# SCH_swissarmyknife_2024-05-07.net
KiCad netlist of a schematic drawn in EasyEDA
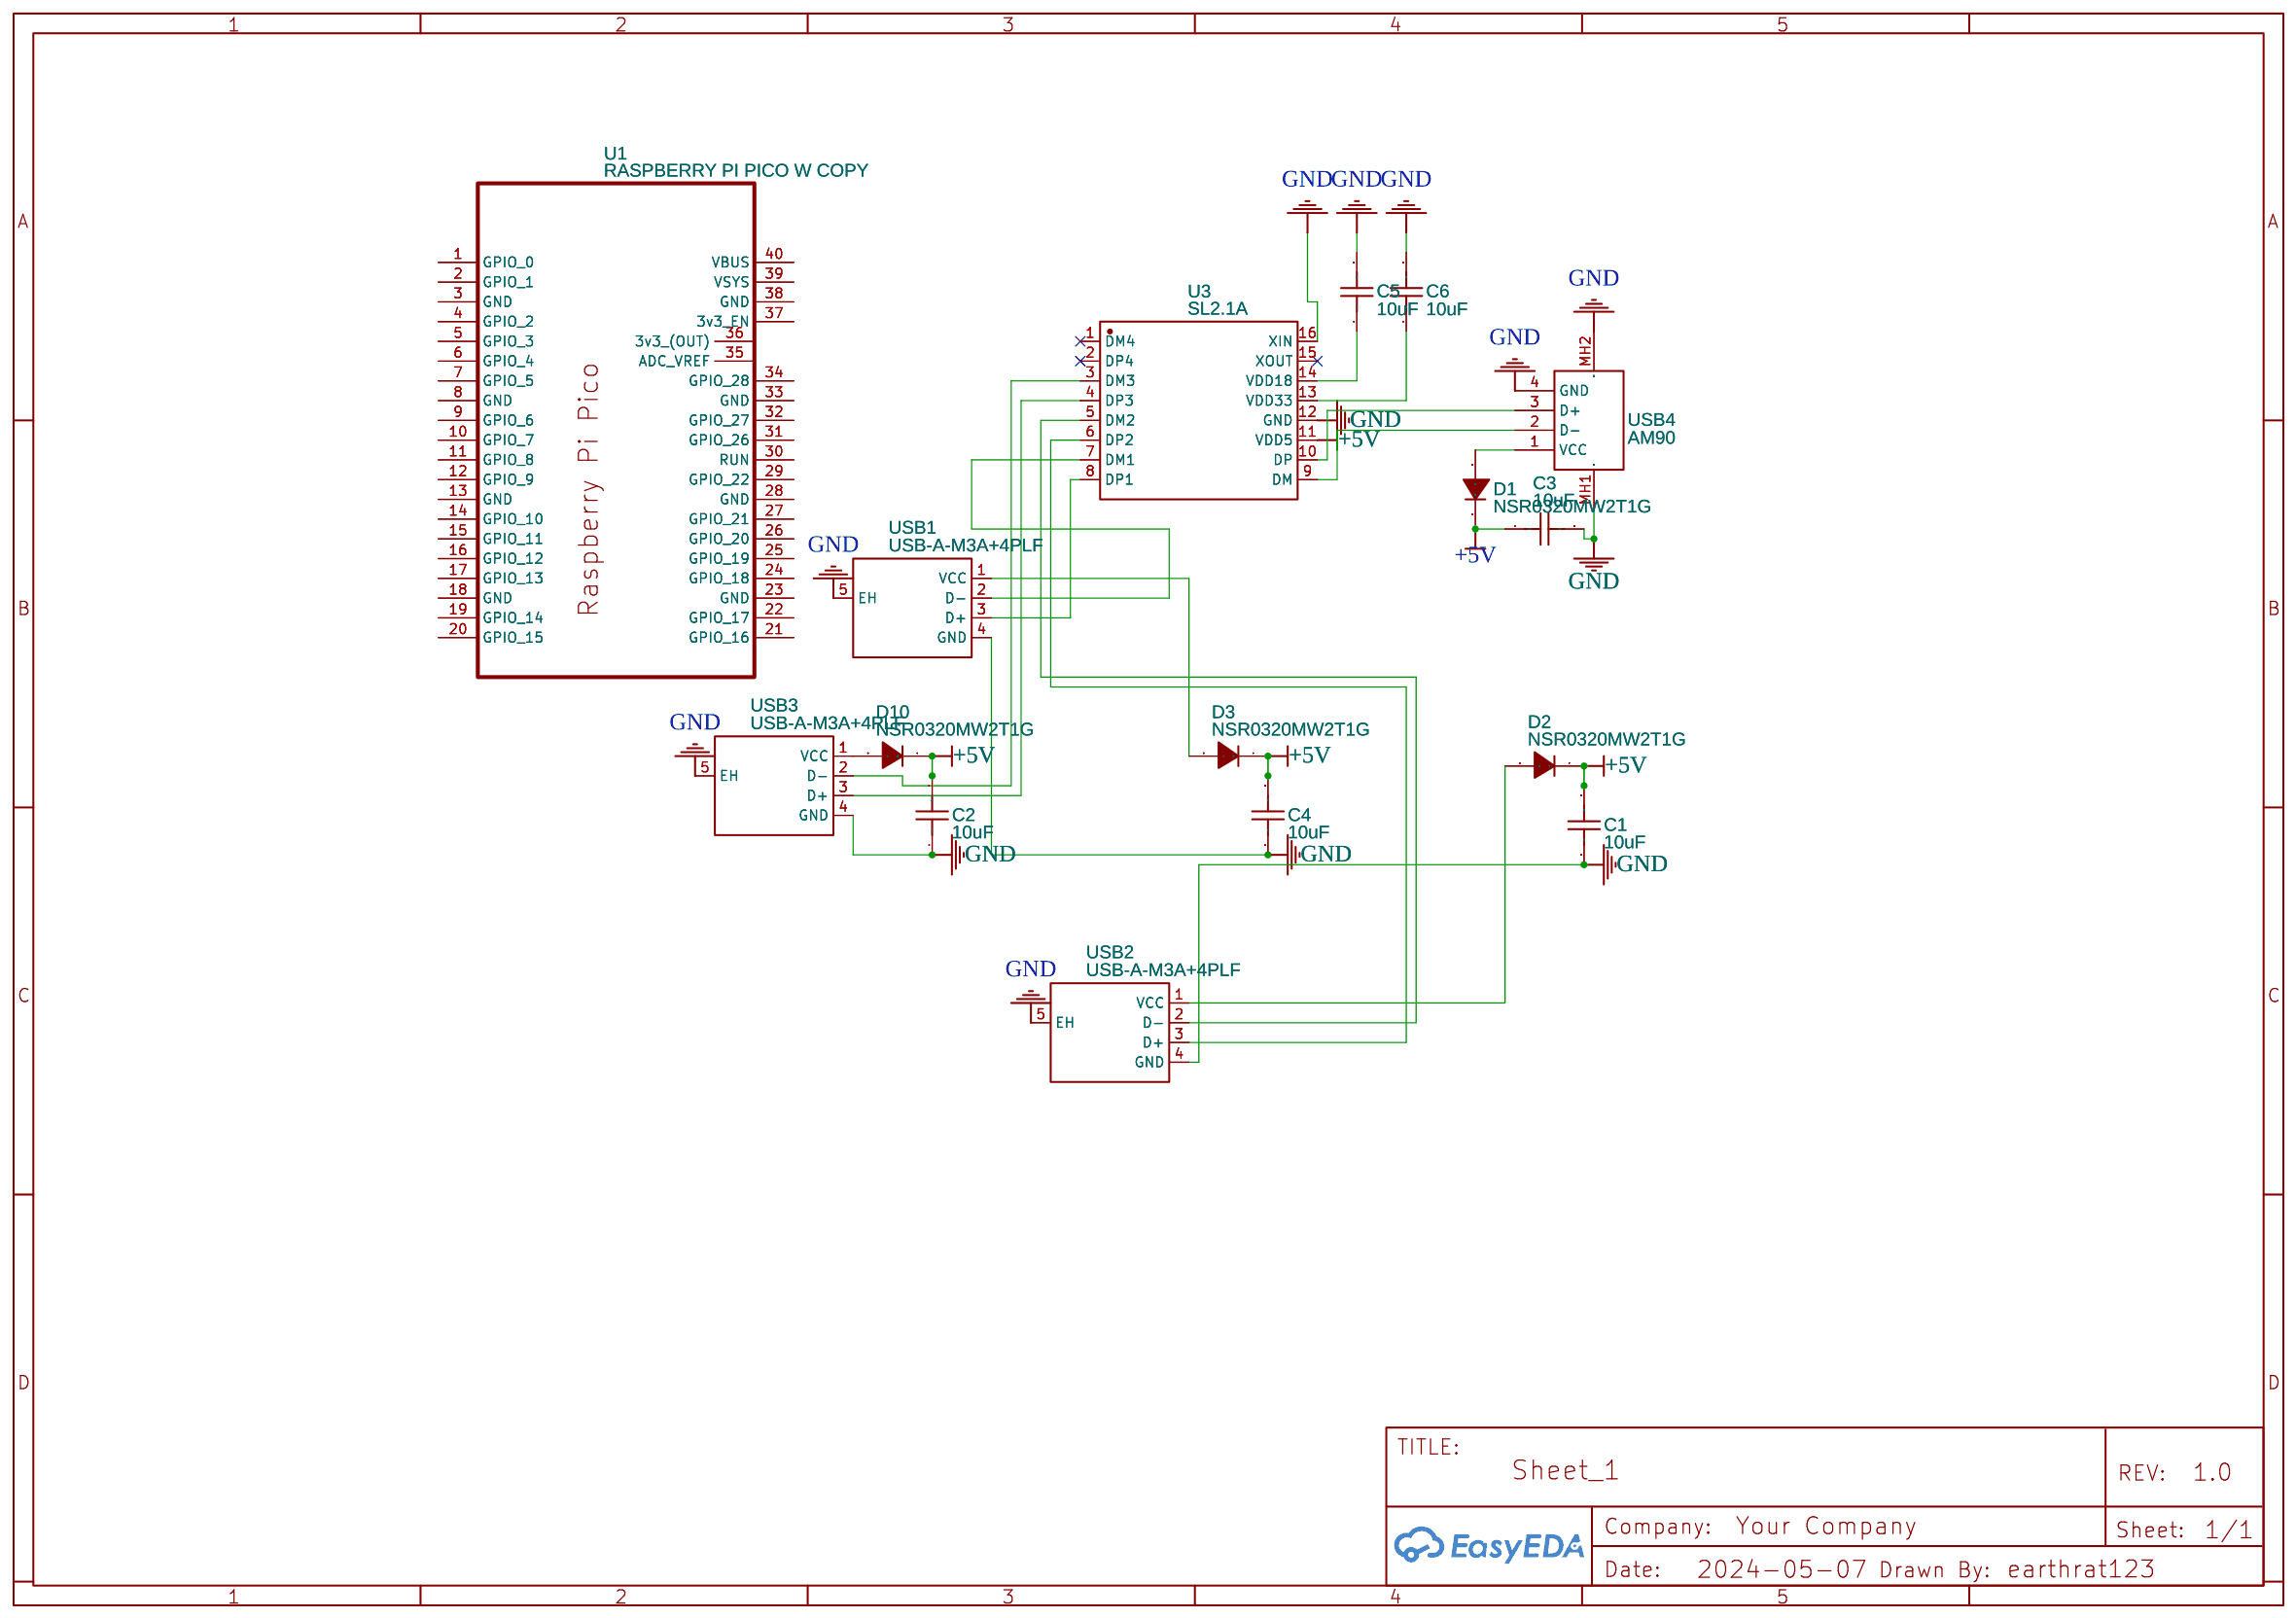
[diagram p0: schematic sheet]

(export (version "E")
  (design (tool "Eeschema 10.0.6"))
  (components
    (comp (ref "C1")
      (value "10uF")
      (fields
        (field (name "Manufacturer Part") "CL10A106KP8NNNC")
        (field (name "Manufacturer") "SAMSUNG(三星)")
      )
      (libsource (lib "") (part "CL10A106KP8NNNC"))
    )
    (comp (ref "C2")
      (value "10uF")
      (fields
        (field (name "Manufacturer Part") "CL10A106KP8NNNC")
        (field (name "Manufacturer") "SAMSUNG(三星)")
      )
      (libsource (lib "") (part "CL10A106KP8NNNC"))
    )
    (comp (ref "C3")
      (value "10uF")
      (fields
        (field (name "Manufacturer Part") "CL10A106KP8NNNC")
        (field (name "Manufacturer") "SAMSUNG(三星)")
      )
      (libsource (lib "") (part "CL10A106KP8NNNC_1"))
    )
    (comp (ref "C4")
      (value "10uF")
      (fields
        (field (name "Manufacturer Part") "CL10A106KP8NNNC")
        (field (name "Manufacturer") "SAMSUNG(三星)")
      )
      (libsource (lib "") (part "CL10A106KP8NNNC"))
    )
    (comp (ref "C5")
      (value "10uF")
      (fields
        (field (name "Manufacturer Part") "CL10A106KP8NNNC")
        (field (name "Manufacturer") "SAMSUNG(三星)")
      )
      (libsource (lib "") (part "CL10A106KP8NNNC"))
    )
    (comp (ref "C6")
      (value "10uF")
      (fields
        (field (name "Manufacturer Part") "CL10A106KP8NNNC")
        (field (name "Manufacturer") "SAMSUNG(三星)")
      )
      (libsource (lib "") (part "CL10A106KP8NNNC"))
    )
    (comp (ref "D1")
      (value "NSR0320MW2T1G")
      (fields (field (name "Manufacturer") "onsemi(安森美)"))
      (libsource (lib "") (part "NSR0320MW2T1G_1"))
    )
    (comp (ref "D2")
      (value "NSR0320MW2T1G")
      (fields (field (name "Manufacturer") "onsemi(安森美)"))
      (libsource (lib "") (part "NSR0320MW2T1G"))
    )
    (comp (ref "D3")
      (value "NSR0320MW2T1G")
      (fields (field (name "Manufacturer") "onsemi(安森美)"))
      (libsource (lib "") (part "NSR0320MW2T1G"))
    )
    (comp (ref "D10")
      (value "NSR0320MW2T1G")
      (fields (field (name "Manufacturer") "onsemi(安森美)"))
      (libsource (lib "") (part "NSR0320MW2T1G"))
    )
    (comp (ref "U1")
      (value "RASPBERRY PI PICO W COPY")
      (libsource (lib "") (part "RASPBERRY PI PICO W COPY"))
    )
    (comp (ref "U3")
      (value "SL2.1A")
      (fields (field (name "Manufacturer") "CoreChips(和芯润德)"))
      (libsource (lib "") (part "SL2.1A"))
    )
    (comp (ref "USB1")
      (value "USB-A-M3A+4PLF")
      (fields (field (name "Manufacturer") "JINJIA(金佳)"))
      (libsource (lib "") (part "USB-A-M3A+4PLF"))
    )
    (comp (ref "USB2")
      (value "USB-A-M3A+4PLF")
      (fields (field (name "Manufacturer") "JINJIA(金佳)"))
      (libsource (lib "") (part "USB-A-M3A+4PLF"))
    )
    (comp (ref "USB3")
      (value "USB-A-M3A+4PLF")
      (fields (field (name "Manufacturer") "JINJIA(金佳)"))
      (libsource (lib "") (part "USB-A-M3A+4PLF"))
    )
    (comp (ref "USB4")
      (value "AM90")
      (fields (field (name "Manufacturer") "SHOU HAN(首韩)"))
      (libsource (lib "") (part "AM90"))
    )
  )
  (nets
    (net (code "1") (name "+5V") (class "Default")
      (node (ref "C1") (pin "2") (pinfunction "2_2") (pintype "unspecified"))
      (node (ref "C2") (pin "2") (pinfunction "2_2") (pintype "unspecified"))
      (node (ref "C3") (pin "1") (pinfunction "1_1") (pintype "unspecified"))
      (node (ref "C4") (pin "2") (pinfunction "2_2") (pintype "unspecified"))
      (node (ref "D1") (pin "1") (pinfunction "C_1") (pintype "unspecified"))
      (node (ref "D10") (pin "1") (pinfunction "C_1") (pintype "unspecified"))
      (node (ref "D2") (pin "1") (pinfunction "C_1") (pintype "unspecified"))
      (node (ref "D3") (pin "1") (pinfunction "C_1") (pintype "unspecified"))
      (node (ref "U3") (pin "11") (pinfunction "VDD5_11") (pintype "unspecified"))
    )
    (net (code "2") (name "GND") (class "Default")
      (node (ref "C1") (pin "1") (pinfunction "1_1") (pintype "unspecified"))
      (node (ref "C2") (pin "1") (pinfunction "1_1") (pintype "unspecified"))
      (node (ref "C3") (pin "2") (pinfunction "2_2") (pintype "unspecified"))
      (node (ref "C4") (pin "1") (pinfunction "1_1") (pintype "unspecified"))
      (node (ref "C5") (pin "2") (pinfunction "2_2") (pintype "unspecified"))
      (node (ref "C6") (pin "2") (pinfunction "2_2") (pintype "unspecified"))
      (node (ref "U3") (pin "12") (pinfunction "GND_12") (pintype "unspecified"))
      (node (ref "U3") (pin "16") (pinfunction "XIN_16") (pintype "unspecified"))
      (node (ref "USB1") (pin "4") (pinfunction "GND_4") (pintype "input"))
      (node (ref "USB1") (pin "5") (pinfunction "EH_5") (pintype "unspecified"))
      (node (ref "USB2") (pin "4") (pinfunction "GND_4") (pintype "input"))
      (node (ref "USB2") (pin "5") (pinfunction "EH_5") (pintype "unspecified"))
      (node (ref "USB3") (pin "4") (pinfunction "GND_4") (pintype "input"))
      (node (ref "USB3") (pin "5") (pinfunction "EH_5") (pintype "unspecified"))
      (node (ref "USB4") (pin "4") (pinfunction "GND_4") (pintype "input"))
      (node (ref "USB4") (pin "MH1") (pinfunction "MH1_MH1") (pintype "unspecified"))
      (node (ref "USB4") (pin "MH2") (pinfunction "MH2_MH2") (pintype "unspecified"))
    )
    (net (code "3") (name "Net-(D1-A)") (class "Default")
      (node (ref "D1") (pin "2") (pinfunction "A_2") (pintype "unspecified"))
      (node (ref "USB4") (pin "1") (pinfunction "VCC_1") (pintype "input"))
    )
    (net (code "4") (name "Net-(D2-A)") (class "Default")
      (node (ref "D2") (pin "2") (pinfunction "A_2") (pintype "unspecified"))
      (node (ref "USB2") (pin "1") (pinfunction "VCC_1") (pintype "input"))
    )
    (net (code "5") (name "Net-(D3-A)") (class "Default")
      (node (ref "D3") (pin "2") (pinfunction "A_2") (pintype "unspecified"))
      (node (ref "USB1") (pin "1") (pinfunction "VCC_1") (pintype "input"))
    )
    (net (code "6") (name "Net-(D10-A)") (class "Default")
      (node (ref "D10") (pin "2") (pinfunction "A_2") (pintype "unspecified"))
      (node (ref "USB3") (pin "1") (pinfunction "VCC_1") (pintype "input"))
    )
    (net (code "7") (name "Net-(U3-DM)") (class "Default")
      (node (ref "U3") (pin "9") (pinfunction "DM_9") (pintype "unspecified"))
      (node (ref "USB4") (pin "2") (pinfunction "D-_2") (pintype "input"))
    )
    (net (code "8") (name "Net-(U3-DM1)") (class "Default")
      (node (ref "U3") (pin "7") (pinfunction "DM1_7") (pintype "unspecified"))
      (node (ref "USB1") (pin "2") (pinfunction "D-_2") (pintype "input"))
    )
    (net (code "9") (name "Net-(U3-DM2)") (class "Default")
      (node (ref "U3") (pin "5") (pinfunction "DM2_5") (pintype "unspecified"))
      (node (ref "USB2") (pin "2") (pinfunction "D-_2") (pintype "input"))
    )
    (net (code "10") (name "Net-(U3-DM3)") (class "Default")
      (node (ref "U3") (pin "3") (pinfunction "DM3_3") (pintype "unspecified"))
      (node (ref "USB3") (pin "2") (pinfunction "D-_2") (pintype "input"))
    )
    (net (code "11") (name "Net-(U3-DP)") (class "Default")
      (node (ref "U3") (pin "10") (pinfunction "DP_10") (pintype "unspecified"))
      (node (ref "USB4") (pin "3") (pinfunction "D+_3") (pintype "input"))
    )
    (net (code "12") (name "Net-(U3-DP1)") (class "Default")
      (node (ref "U3") (pin "8") (pinfunction "DP1_8") (pintype "unspecified"))
      (node (ref "USB1") (pin "3") (pinfunction "D+_3") (pintype "input"))
    )
    (net (code "13") (name "Net-(U3-DP2)") (class "Default")
      (node (ref "U3") (pin "6") (pinfunction "DP2_6") (pintype "unspecified"))
      (node (ref "USB2") (pin "3") (pinfunction "D+_3") (pintype "input"))
    )
    (net (code "14") (name "Net-(U3-DP3)") (class "Default")
      (node (ref "U3") (pin "4") (pinfunction "DP3_4") (pintype "unspecified"))
      (node (ref "USB3") (pin "3") (pinfunction "D+_3") (pintype "input"))
    )
    (net (code "15") (name "Net-(U3-VDD18)") (class "Default")
      (node (ref "C5") (pin "1") (pinfunction "1_1") (pintype "unspecified"))
      (node (ref "U3") (pin "14") (pinfunction "VDD18_14") (pintype "unspecified"))
    )
    (net (code "16") (name "Net-(U3-VDD33)") (class "Default")
      (node (ref "C6") (pin "1") (pinfunction "1_1") (pintype "unspecified"))
      (node (ref "U3") (pin "13") (pinfunction "VDD33_13") (pintype "unspecified"))
    )
    (net (code "17") (name "unconnected-(U1-3v3_(OUT)-Pad36)") (class "Default")
      (node (ref "U1") (pin "36") (pinfunction "3v3_(OUT)_36") (pintype "unspecified"))
    )
    (net (code "18") (name "unconnected-(U1-3v3_EN-Pad37)") (class "Default")
      (node (ref "U1") (pin "37") (pinfunction "3v3_EN_37") (pintype "unspecified"))
    )
    (net (code "19") (name "unconnected-(U1-ADC_VREF-Pad35)") (class "Default")
      (node (ref "U1") (pin "35") (pinfunction "ADC_VREF_35") (pintype "unspecified"))
    )
    (net (code "20") (name "unconnected-(U1-GND-Pad3)") (class "Default")
      (node (ref "U1") (pin "3") (pinfunction "GND_3") (pintype "unspecified"))
    )
    (net (code "21") (name "unconnected-(U1-GND-Pad8)") (class "Default")
      (node (ref "U1") (pin "8") (pinfunction "GND_8") (pintype "unspecified"))
    )
    (net (code "22") (name "unconnected-(U1-GND-Pad13)") (class "Default")
      (node (ref "U1") (pin "13") (pinfunction "GND_13") (pintype "unspecified"))
    )
    (net (code "23") (name "unconnected-(U1-GND-Pad18)") (class "Default")
      (node (ref "U1") (pin "18") (pinfunction "GND_18") (pintype "unspecified"))
    )
    (net (code "24") (name "unconnected-(U1-GND-Pad23)") (class "Default")
      (node (ref "U1") (pin "23") (pinfunction "GND_23") (pintype "unspecified"))
    )
    (net (code "25") (name "unconnected-(U1-GND-Pad28)") (class "Default")
      (node (ref "U1") (pin "28") (pinfunction "GND_28") (pintype "unspecified"))
    )
    (net (code "26") (name "unconnected-(U1-GND-Pad33)") (class "Default")
      (node (ref "U1") (pin "33") (pinfunction "GND_33") (pintype "unspecified"))
    )
    (net (code "27") (name "unconnected-(U1-GND-Pad38)") (class "Default")
      (node (ref "U1") (pin "38") (pinfunction "GND_38") (pintype "unspecified"))
    )
    (net (code "28") (name "unconnected-(U1-GPIO_0-Pad1)") (class "Default")
      (node (ref "U1") (pin "1") (pinfunction "GPIO_0_1") (pintype "unspecified"))
    )
    (net (code "29") (name "unconnected-(U1-GPIO_1-Pad2)") (class "Default")
      (node (ref "U1") (pin "2") (pinfunction "GPIO_1_2") (pintype "unspecified"))
    )
    (net (code "30") (name "unconnected-(U1-GPIO_2-Pad4)") (class "Default")
      (node (ref "U1") (pin "4") (pinfunction "GPIO_2_4") (pintype "unspecified"))
    )
    (net (code "31") (name "unconnected-(U1-GPIO_3-Pad5)") (class "Default")
      (node (ref "U1") (pin "5") (pinfunction "GPIO_3_5") (pintype "unspecified"))
    )
    (net (code "32") (name "unconnected-(U1-GPIO_4-Pad6)") (class "Default")
      (node (ref "U1") (pin "6") (pinfunction "GPIO_4_6") (pintype "unspecified"))
    )
    (net (code "33") (name "unconnected-(U1-GPIO_5-Pad7)") (class "Default")
      (node (ref "U1") (pin "7") (pinfunction "GPIO_5_7") (pintype "unspecified"))
    )
    (net (code "34") (name "unconnected-(U1-GPIO_6-Pad9)") (class "Default")
      (node (ref "U1") (pin "9") (pinfunction "GPIO_6_9") (pintype "unspecified"))
    )
    (net (code "35") (name "unconnected-(U1-GPIO_7-Pad10)") (class "Default")
      (node (ref "U1") (pin "10") (pinfunction "GPIO_7_10") (pintype "unspecified"))
    )
    (net (code "36") (name "unconnected-(U1-GPIO_8-Pad11)") (class "Default")
      (node (ref "U1") (pin "11") (pinfunction "GPIO_8_11") (pintype "unspecified"))
    )
    (net (code "37") (name "unconnected-(U1-GPIO_9-Pad12)") (class "Default")
      (node (ref "U1") (pin "12") (pinfunction "GPIO_9_12") (pintype "unspecified"))
    )
    (net (code "38") (name "unconnected-(U1-GPIO_10-Pad14)") (class "Default")
      (node (ref "U1") (pin "14") (pinfunction "GPIO_10_14") (pintype "unspecified"))
    )
    (net (code "39") (name "unconnected-(U1-GPIO_11-Pad15)") (class "Default")
      (node (ref "U1") (pin "15") (pinfunction "GPIO_11_15") (pintype "unspecified"))
    )
    (net (code "40") (name "unconnected-(U1-GPIO_12-Pad16)") (class "Default")
      (node (ref "U1") (pin "16") (pinfunction "GPIO_12_16") (pintype "unspecified"))
    )
    (net (code "41") (name "unconnected-(U1-GPIO_13-Pad17)") (class "Default")
      (node (ref "U1") (pin "17") (pinfunction "GPIO_13_17") (pintype "unspecified"))
    )
    (net (code "42") (name "unconnected-(U1-GPIO_14-Pad19)") (class "Default")
      (node (ref "U1") (pin "19") (pinfunction "GPIO_14_19") (pintype "unspecified"))
    )
    (net (code "43") (name "unconnected-(U1-GPIO_15-Pad20)") (class "Default")
      (node (ref "U1") (pin "20") (pinfunction "GPIO_15_20") (pintype "unspecified"))
    )
    (net (code "44") (name "unconnected-(U1-GPIO_16-Pad21)") (class "Default")
      (node (ref "U1") (pin "21") (pinfunction "GPIO_16_21") (pintype "unspecified"))
    )
    (net (code "45") (name "unconnected-(U1-GPIO_17-Pad22)") (class "Default")
      (node (ref "U1") (pin "22") (pinfunction "GPIO_17_22") (pintype "unspecified"))
    )
    (net (code "46") (name "unconnected-(U1-GPIO_18-Pad24)") (class "Default")
      (node (ref "U1") (pin "24") (pinfunction "GPIO_18_24") (pintype "unspecified"))
    )
    (net (code "47") (name "unconnected-(U1-GPIO_19-Pad25)") (class "Default")
      (node (ref "U1") (pin "25") (pinfunction "GPIO_19_25") (pintype "unspecified"))
    )
    (net (code "48") (name "unconnected-(U1-GPIO_20-Pad26)") (class "Default")
      (node (ref "U1") (pin "26") (pinfunction "GPIO_20_26") (pintype "unspecified"))
    )
    (net (code "49") (name "unconnected-(U1-GPIO_21-Pad27)") (class "Default")
      (node (ref "U1") (pin "27") (pinfunction "GPIO_21_27") (pintype "unspecified"))
    )
    (net (code "50") (name "unconnected-(U1-GPIO_22-Pad29)") (class "Default")
      (node (ref "U1") (pin "29") (pinfunction "GPIO_22_29") (pintype "unspecified"))
    )
    (net (code "51") (name "unconnected-(U1-GPIO_26-Pad31)") (class "Default")
      (node (ref "U1") (pin "31") (pinfunction "GPIO_26_31") (pintype "unspecified"))
    )
    (net (code "52") (name "unconnected-(U1-GPIO_27-Pad32)") (class "Default")
      (node (ref "U1") (pin "32") (pinfunction "GPIO_27_32") (pintype "unspecified"))
    )
    (net (code "53") (name "unconnected-(U1-GPIO_28-Pad34)") (class "Default")
      (node (ref "U1") (pin "34") (pinfunction "GPIO_28_34") (pintype "unspecified"))
    )
    (net (code "54") (name "unconnected-(U1-RUN-Pad30)") (class "Default")
      (node (ref "U1") (pin "30") (pinfunction "RUN_30") (pintype "unspecified"))
    )
    (net (code "55") (name "unconnected-(U1-VBUS-Pad40)") (class "Default")
      (node (ref "U1") (pin "40") (pinfunction "VBUS_40") (pintype "unspecified"))
    )
    (net (code "56") (name "unconnected-(U1-VSYS-Pad39)") (class "Default")
      (node (ref "U1") (pin "39") (pinfunction "VSYS_39") (pintype "unspecified"))
    )
    (net (code "57") (name "unconnected-(U3-DM4-Pad1)") (class "Default")
      (node (ref "U3") (pin "1") (pinfunction "DM4_1") (pintype "unspecified+no_connect"))
    )
    (net (code "58") (name "unconnected-(U3-DP4-Pad2)") (class "Default")
      (node (ref "U3") (pin "2") (pinfunction "DP4_2") (pintype "unspecified+no_connect"))
    )
    (net (code "59") (name "unconnected-(U3-XOUT-Pad15)") (class "Default")
      (node (ref "U3") (pin "15") (pinfunction "XOUT_15") (pintype "unspecified+no_connect"))
    )
  )
)
